# FontesLineares.net
KiCad netlist of a schematic drawn in Altium Designer
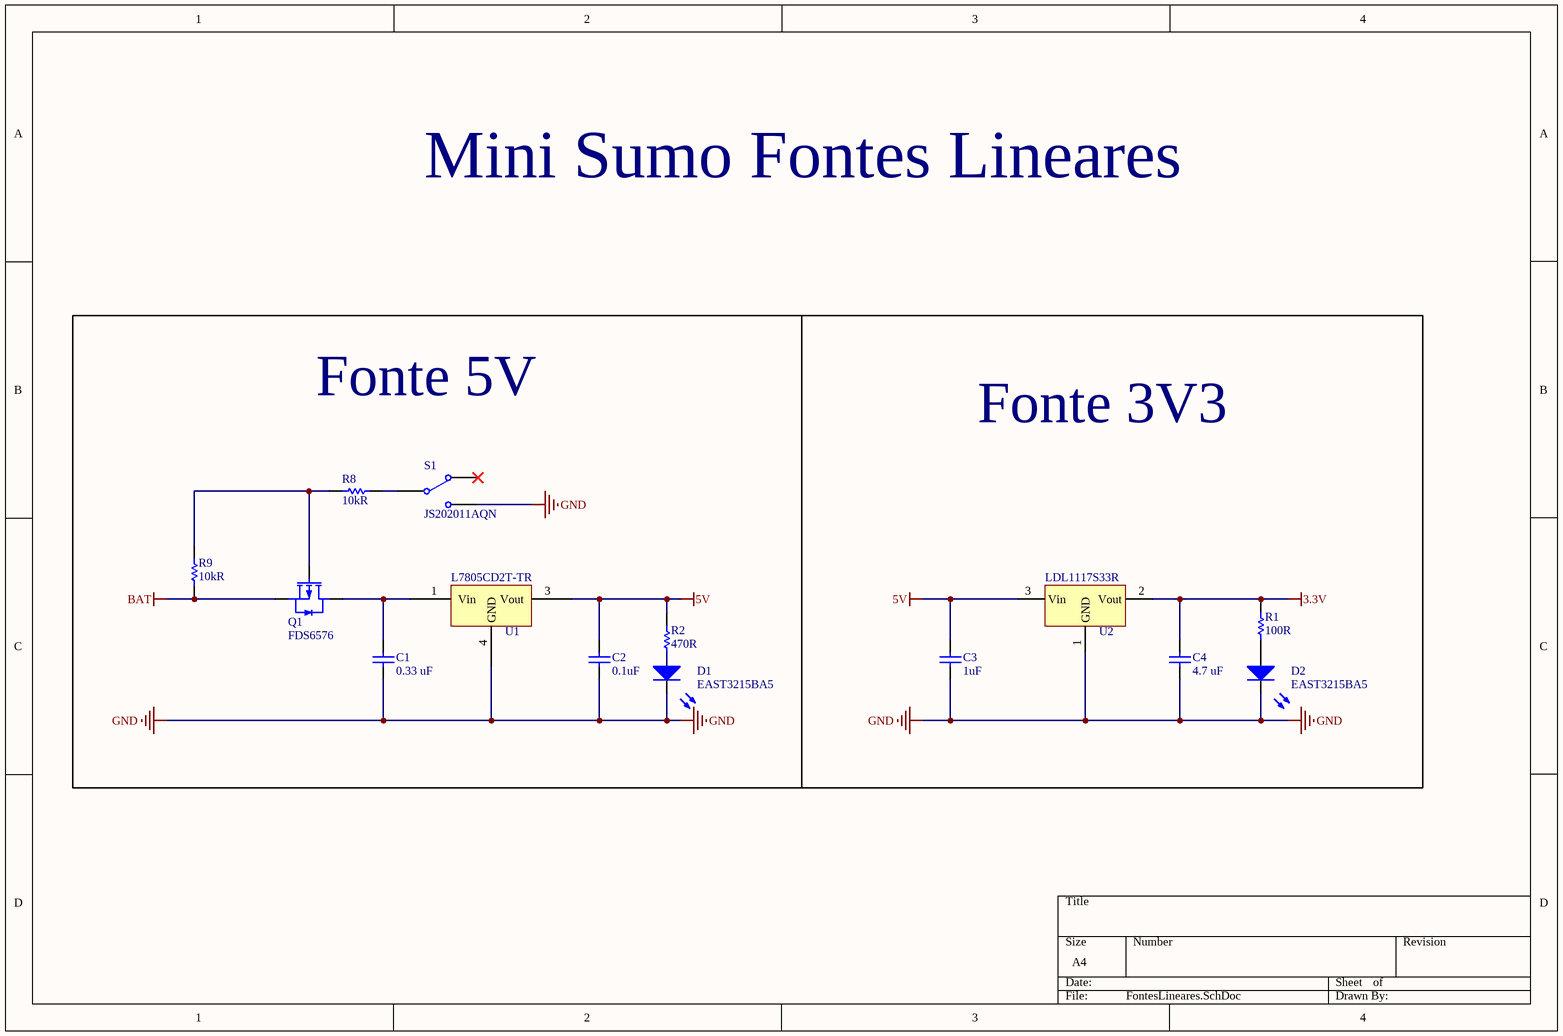
[diagram p0: FontesLineares.SchDoc]

(export (version "E")
  (design (tool "Eeschema 10.0.6"))
  (components
    (comp (ref "C1")
      (value "0.33 uF")
      (footprint "C0805")
      (description "CAP CER 0.33UF 25V X7R 0805")
      (fields
        (field (name "MANUFACTURER") "Murata Eletronics")
        (field (name "PART NUMBER") "GCM21BR71E334KA37K")
        (field (name "LIBRARY CONTROL - PERSON THAT CHECKED FOOTPRINT") "Nikaum")
        (field (name "LIBRARY CONTROL - PERSON THAT CHECKED SCHEMATIC") "Nikaum")
        (field (name "LIBRARY CONTROL - PERSON THAT DID THE LAST UPDATE FOOTPRINT") "Nikaum")
        (field (name "LIBRARY CONTROL - PERSON THAT DID THE LAST UPDATE SCHEMATIC") "Nikaum")
      )
      (libsource (lib "Uai!Tecas") (part "GCM21BR71E334KA37K"))
    )
    (comp (ref "C2")
      (value "0.1uF")
      (footprint "C0805")
      (description "CAP CER 0.1uF 25V X7R 0805")
      (fields
        (field (name "MANUFACTURER") "Kemet")
        (field (name "PART NUMBER") "C0805C104M3RACTU")
        (field (name "LIBRARY CONTROL - PERSON THAT CHECKED SCHEMATIC") "Guilherme")
        (field (name "LIBRARY CONTROL - PERSON THAT DID THE LAST UPDATE SCHEMATIC") "Marcos")
      )
      (libsource (lib "Uai!Tecas") (part "C0805C104M3RACTU"))
    )
    (comp (ref "C3")
      (value "1uF")
      (footprint "C0603")
      (description "CAP CER 1UF 25V X7R 0603")
      (libsource (lib "Uai!Tecas") (part "Capacitor Model"))
    )
    (comp (ref "C4")
      (value "4.7 uF")
      (footprint "C0805")
      (description "CAP CER 4.7uF 25V X5R 0805")
      (fields
        (field (name "MANUFACTURER") "MURATA ELECTRONICS")
        (field (name "PART NUMBER") "GRM219R61E475KA73D")
        (field (name "LIBRARY CONTROL - PERSON THAT CHECKED FOOTPRINT") "Cage")
        (field (name "LIBRARY CONTROL - PERSON THAT CHECKED SCHEMATIC") "Cage")
        (field (name "LIBRARY CONTROL - PERSON THAT DID THE LAST UPDATE FOOTPRINT") "Cage")
        (field (name "LIBRARY CONTROL - PERSON THAT DID THE LAST UPDATE SCHEMATIC") "Cage")
      )
      (libsource (lib "Uai!Tecas") (part "GRM219R61E475KA73D"))
    )
    (comp (ref "D1")
      (value "EAST3215BA5")
      (footprint "DIODO_2-SMD-3215")
      (description "LED 75mW BLUE 45MCD 3215")
      (fields
        (field (name "MANUFACTURER") "Everlight Electronics")
        (field (name "LIBRARY CONTROL - PERSON THAT DID THE LAST UPDATE FOOTPRINT") "Stéfany (Ster)")
        (field (name "LIBRARY CONTROL - PERSON THAT DID THE LAST UPDATE SCHEMATIC") "Stéfany (Ster)")
        (field (name "LIBRARY CONTROL - PERSON THAT CHECKED SCHEMATIC") "Lucas")
        (field (name "LIBRARY CONTROL - PERSON THAT CHECKED FOOTPRINT") "Lucas")
      )
      (libsource (lib "Uai!Rrior") (part "EAST3215BA5"))
    )
    (comp (ref "D2")
      (value "EAST3215BA5")
      (footprint "DIODO_2-SMD-3215")
      (description "LED 75mW BLUE 45MCD 3215")
      (fields
        (field (name "MANUFACTURER") "Everlight Electronics")
        (field (name "LIBRARY CONTROL - PERSON THAT DID THE LAST UPDATE FOOTPRINT") "Stéfany (Ster)")
        (field (name "LIBRARY CONTROL - PERSON THAT DID THE LAST UPDATE SCHEMATIC") "Stéfany (Ster)")
        (field (name "LIBRARY CONTROL - PERSON THAT CHECKED SCHEMATIC") "Lucas")
        (field (name "LIBRARY CONTROL - PERSON THAT CHECKED FOOTPRINT") "Lucas")
      )
      (libsource (lib "Uai!Rrior") (part "EAST3215BA5"))
    )
    (comp (ref "Q1")
      (value "FDS6576")
      (footprint "SOIC-8")
      (description "MOSFET P-CH 20V 11A SOIC-8")
      (fields (field (name "PART NUMBER") "SOIC-8") (field (name "MANUFACTURER") "onsemi / Fairchild"))
      (libsource (lib "Uai!Tecas") (part "FDS6576"))
    )
    (comp (ref "R1")
      (value "100R")
      (footprint "RESISTOR_0805")
      (description "RES SMD 100 OHM 1% 1/8W 0805")
      (fields
        (field (name "PART NUMBER") "CRCW0805100RFKEA")
        (field (name "TOLERANCE") "1 %")
        (field (name "LIBRARY CONTROL - PERSON THAT DID THE LAST UPDATE FOOTPRINT") "Dalarme")
        (field (name "LIBRARY CONTROL - PERSON THAT DID THE LAST UPDATE SCHEMATIC") "Marcos")
        (field (name "LIBRARY CONTROL - PERSON THAT CHECKED SCHEMATIC") "Marcos")
      )
      (libsource (lib "Uai!Rrior") (part "PR03000201000JAC00"))
    )
    (comp (ref "R2")
      (value "470R")
      (footprint "RESISTOR_0805")
      (description "RES SMD 470 OHM 5% 1/8W 0805")
      (fields
        (field (name "PART NUMBER") "667-ERJ-6GEYJ471V")
        (field (name "MANUFACTURER") "Panasonic")
        (field (name "LIBRARY CONTROL - PERSON THAT CHECKED SCHEMATIC") "Marcos")
        (field (name "LIBRARY CONTROL - PERSON THAT DID THE LAST UPDATE FOOTPRINT") "Dalarme")
        (field (name "LIBRARY CONTROL - PERSON THAT DID THE LAST UPDATE SCHEMATIC") "Marcos")
      )
      (libsource (lib "Uai!Rrior") (part "PR03000201000JAC00"))
    )
    (comp (ref "R8")
      (value "10kR")
      (footprint "RESISTOR_0603")
      (description "RES SMD 10K OHM 5% 1/10W 0603")
      (fields
        (field (name "MANUFACTURER") "Yageo")
        (field (name "PART NUMBER") "RC0603JR-0710KL")
        (field (name "LIBRARY CONTROL - PERSON THAT CHECKED SCHEMATIC") "Marcos")
        (field (name "LIBRARY CONTROL - PERSON THAT DID THE LAST UPDATE FOOTPRINT") "Dalarme")
        (field (name "LIBRARY CONTROL - PERSON THAT DID THE LAST UPDATE SCHEMATIC") "Marcos")
      )
      (libsource (lib "Uai!Tecas") (part "RC0603JR-0710KL"))
    )
    (comp (ref "R9")
      (value "10kR")
      (footprint "RESISTOR_0603")
      (description "RES SMD 10K OHM 5% 1/10W 0603")
      (fields
        (field (name "MANUFACTURER") "Yageo")
        (field (name "PART NUMBER") "RC0603JR-0710KL")
        (field (name "LIBRARY CONTROL - PERSON THAT CHECKED SCHEMATIC") "Marcos")
        (field (name "LIBRARY CONTROL - PERSON THAT DID THE LAST UPDATE FOOTPRINT") "Dalarme")
        (field (name "LIBRARY CONTROL - PERSON THAT DID THE LAST UPDATE SCHEMATIC") "Marcos")
      )
      (libsource (lib "Uai!Tecas") (part "RC0603JR-0710KL"))
    )
    (comp (ref "S1")
      (value "JS202011AQN")
      (footprint "SOIC6_THRU_HOLE")
      (description "SLIDE SWITCH DPDT 0.3A 30VDC THRU ROLE")
      (fields
        (field (name "MANUFACTURER") "C&K Switches")
        (field (name "LIBRARY CONTROL - PERSON THAT DID THE LAST UPDATE FOOTPRINT") "Lucas")
        (field (name "LIBRARY CONTROL - PERSON THAT DID THE LAST UPDATE SCHEMATIC") "Lucas")
      )
      (libsource (lib "Uai!Tecas") (part "JS202011CQN_1"))
    )
    (comp (ref "U1")
      (value "L7805CD2T-TR")
      (footprint "D2PAK_V2")
      (description "IC REG LINEAR 5V 1A D2PAK")
      (fields
        (field (name "MANUFACTURER") "ST")
        (field (name "LIBRARY CONTROL - PERSON THAT CHECKED FOOTPRINT") "Nícolas")
        (field (name "LIBRARY CONTROL - PERSON THAT CHECKED SCHEMATIC") "Nícolas")
        (field (name "LIBRARY CONTROL - PERSON THAT DID THE LAST UPDATE SCHEMATIC") "Nícolas")
      )
      (libsource (lib "Uai!Tecas") (part "L7805CD2T-TR"))
    )
    (comp (ref "U2")
      (value "LDL1117S33R")
      (footprint "SOT-223-4")
      (description "IC REG LINEAR 3.3V 1.2A SOT-223-4")
      (fields
        (field (name "MANUFACTURER") "STMicroelectronics")
        (field (name "LIBRARY CONTROL - PERSON THAT CHECKED FOOTPRINT") "Nícolas")
        (field (name "LIBRARY CONTROL - PERSON THAT CHECKED SCHEMATIC") "Nícolas")
        (field (name "LIBRARY CONTROL - PERSON THAT DID THE LAST UPDATE FOOTPRINT") "Pierre")
        (field (name "LIBRARY CONTROL - PERSON THAT DID THE LAST UPDATE SCHEMATIC") "Nícolas")
      )
      (libsource (lib "Uai!Tecas") (part "LDL1117S33R"))
    )
  )
  (nets
    (net (code "1") (name "3.3V") (class "Default")
      (node (ref "C4") (pin "2") (pinfunction "2_2") (pintype "passive"))
      (node (ref "R1") (pin "2") (pinfunction "2_2") (pintype "passive"))
      (node (ref "U2") (pin "2") (pinfunction "Vout_2") (pintype "power_in"))
    )
    (net (code "2") (name "5V") (class "Default")
      (node (ref "C2") (pin "2") (pinfunction "2_2") (pintype "passive"))
      (node (ref "C3") (pin "2") (pinfunction "2_2") (pintype "passive"))
      (node (ref "R2") (pin "2") (pinfunction "2_2") (pintype "passive"))
      (node (ref "U1") (pin "3") (pinfunction "Vout_3") (pintype "passive"))
      (node (ref "U2") (pin "3") (pinfunction "Vin_3") (pintype "power_in"))
    )
    (net (code "3") (name "BAT") (class "Default")
      (node (ref "Q1") (pin "S") (pinfunction "S_S") (pintype "passive"))
      (node (ref "R9") (pin "1") (pinfunction "1_1") (pintype "passive"))
    )
    (net (code "4") (name "GND") (class "Default")
      (node (ref "C1") (pin "1") (pinfunction "1_1") (pintype "passive"))
      (node (ref "C2") (pin "1") (pinfunction "1_1") (pintype "passive"))
      (node (ref "C3") (pin "1") (pinfunction "1_1") (pintype "passive"))
      (node (ref "C4") (pin "1") (pinfunction "1_1") (pintype "passive"))
      (node (ref "D1") (pin "C") (pinfunction "C_C") (pintype "passive"))
      (node (ref "D2") (pin "C") (pinfunction "C_C") (pintype "passive"))
      (node (ref "S1") (pin "2") (pinfunction "NO_2") (pintype "passive"))
      (node (ref "U1") (pin "4") (pinfunction "GND_4") (pintype "passive"))
      (node (ref "U2") (pin "1") (pinfunction "GND_1") (pintype "power_in"))
    )
    (net (code "5") (name "Net-(D1-PadA)") (class "Default")
      (node (ref "D1") (pin "A") (pinfunction "A_A") (pintype "passive"))
      (node (ref "R2") (pin "1") (pinfunction "1_1") (pintype "passive"))
    )
    (net (code "6") (name "Net-(D2-PadA)") (class "Default")
      (node (ref "D2") (pin "A") (pinfunction "A_A") (pintype "passive"))
      (node (ref "R1") (pin "1") (pinfunction "1_1") (pintype "passive"))
    )
    (net (code "7") (name "Net-(Q1-PadG)") (class "Default")
      (node (ref "Q1") (pin "G") (pinfunction "G_G") (pintype "passive"))
      (node (ref "R8") (pin "2") (pinfunction "2_2") (pintype "passive"))
      (node (ref "R9") (pin "2") (pinfunction "2_2") (pintype "passive"))
    )
    (net (code "8") (name "Net-(S1-COMMON)") (class "Default")
      (node (ref "R8") (pin "1") (pinfunction "1_1") (pintype "passive"))
      (node (ref "S1") (pin "C") (pinfunction "COMMON_C") (pintype "passive"))
    )
    (net (code "9") (name "Net-(U1-Vin)") (class "Default")
      (node (ref "C1") (pin "2") (pinfunction "2_2") (pintype "passive"))
      (node (ref "Q1") (pin "D") (pinfunction "D_D") (pintype "passive"))
      (node (ref "U1") (pin "1") (pinfunction "Vin_1") (pintype "passive"))
    )
    (net (code "10") (name "unconnected-(S1-Pad1)") (class "Default")
      (node (ref "S1") (pin "1") (pinfunction "1_1") (pintype "passive+no_connect"))
    )
  )
)
